# Schematic.net
KiCad netlist of a schematic drawn in Altium Designer
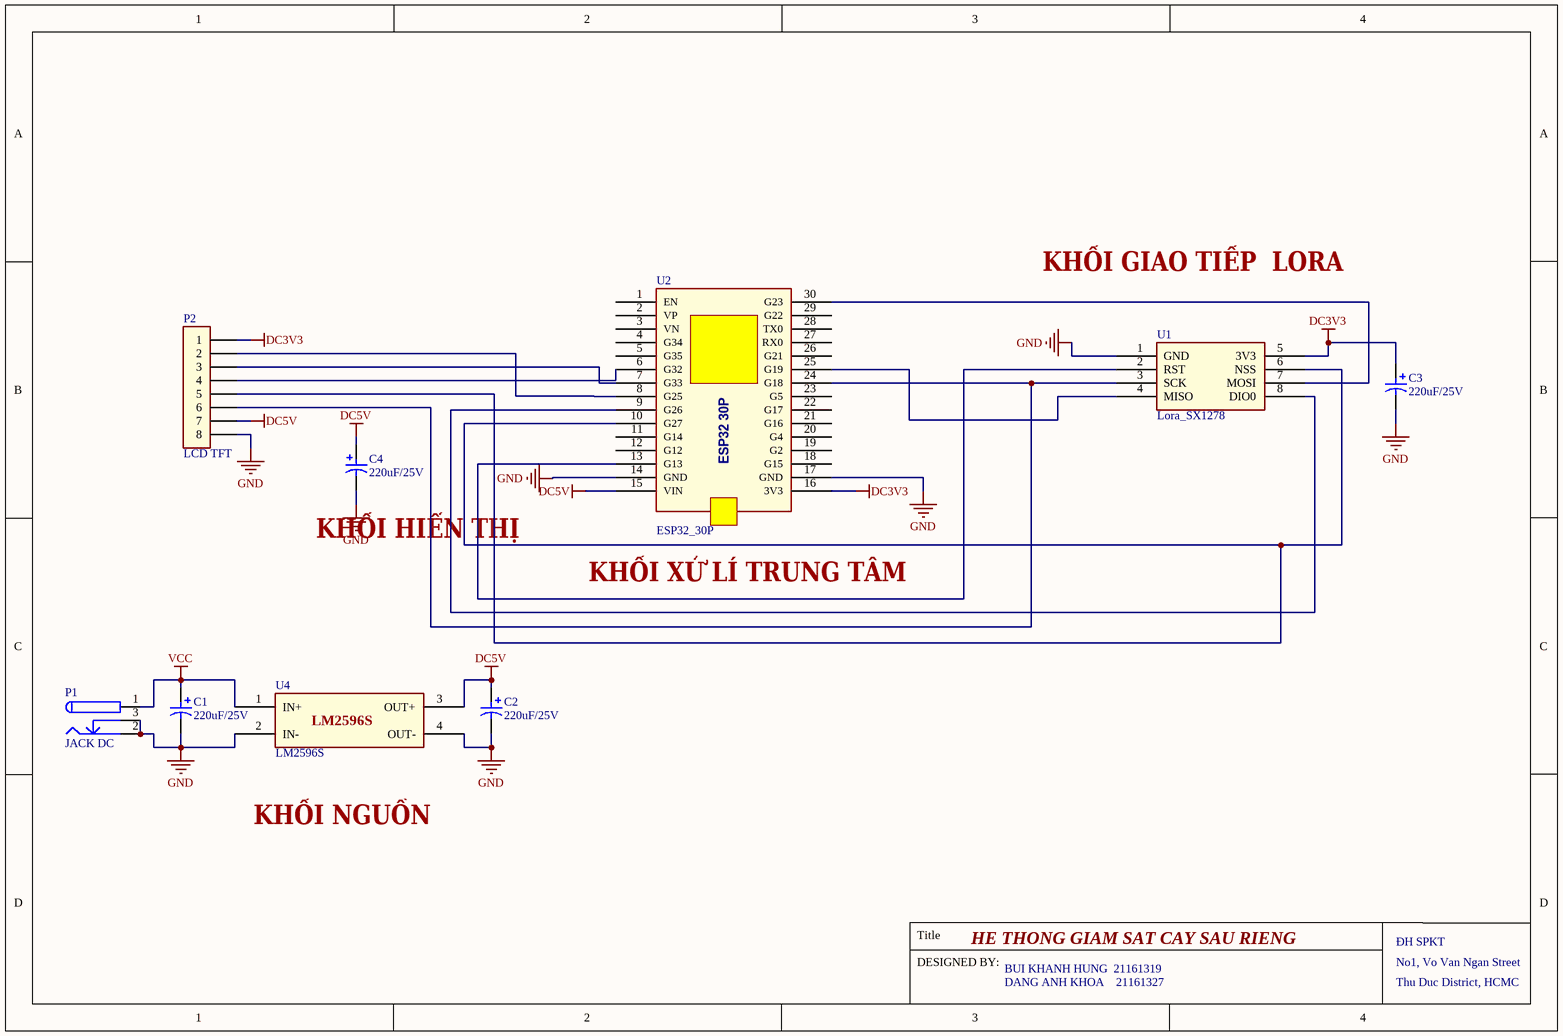
[diagram p0: Schematic.SchDoc]

(export (version "E")
  (design (tool "Eeschema 10.0.6"))
  (components
    (comp (ref "C1")
      (value "220uF/25V")
      (footprint "CAP-ALUM-10x12.5")
      (description "Capacitor Aluminum 220uF 20% 25V Radial")
      (fields (field (name "MPN") "CLA4514"))
      (libsource (lib "SachTranLib") (part "EEUTA1E221"))
    )
    (comp (ref "C2")
      (value "220uF/25V")
      (footprint "CAP-ALUM-10x12.5")
      (description "Capacitor Aluminum 220uF 20% 25V Radial")
      (fields (field (name "MPN") "CLA4514"))
      (libsource (lib "SachTranLib") (part "EEUTA1E221"))
    )
    (comp (ref "C3")
      (value "220uF/25V")
      (footprint "CAP-ALUM-10x12.5")
      (description "Capacitor Aluminum 220uF 20% 25V Radial")
      (fields (field (name "MPN") "CLA4514"))
      (libsource (lib "SachTranLib") (part "EEUTA1E221"))
    )
    (comp (ref "C4")
      (value "220uF/25V")
      (footprint "CAP-ALUM-10x12.5")
      (description "Capacitor Aluminum 220uF 20% 25V Radial")
      (fields (field (name "MPN") "CLA4514"))
      (libsource (lib "") (part "EEUTA1E221_1"))
    )
    (comp (ref "P1")
      (value "JACK DC")
      (footprint "DC5.5/2.1")
      (description "Low Voltage Power Supply Connector")
      (libsource (lib "SachTranLib") (part "DC5.5/2.1"))
    )
    (comp (ref "P2")
      (value "LCD TFT")
      (footprint "B8B-XH-A")
      (description "Connector Header Through Hole 8 position 0.098\" (2.50mm)")
      (libsource (lib "SachTranLib") (part "B8B-XH-A"))
    )
    (comp (ref "U1")
      (value "Lora_SX1278")
      (footprint "Module-LORA-SX1278")
      (description "Module Lora SX1278 RA02 SPI")
      (libsource (lib "SachTranLib") (part "Module-Lora-SX1278-SPI"))
    )
    (comp (ref "U2")
      (value "ESP32_30P")
      (footprint "Kit-ESP32-30P")
      (description "Kit ESP32 30P")
      (libsource (lib "SachTranLib") (part "Kit_ESP32_30P"))
    )
    (comp (ref "U4")
      (value "LM2596S")
      (footprint "Module-LM2596S")
      (description "Module LM2596S")
      (libsource (lib "SachTranLib") (part "Module-LM2596S"))
    )
  )
  (nets
    (net (code "1") (name "DC3V3") (class "Default")
      (node (ref "C3") (pin "1") (pinfunction "1_1") (pintype "passive"))
      (node (ref "P2") (pin "1") (pinfunction "1_1") (pintype "passive"))
      (node (ref "U1") (pin "5") (pinfunction "3V3_5") (pintype "passive"))
      (node (ref "U2") (pin "16") (pinfunction "3V3_16") (pintype "passive"))
    )
    (net (code "2") (name "DC5V") (class "Default")
      (node (ref "C2") (pin "1") (pinfunction "1_1") (pintype "passive"))
      (node (ref "C4") (pin "1") (pinfunction "1_1") (pintype "passive"))
      (node (ref "P2") (pin "7") (pinfunction "7_7") (pintype "passive"))
      (node (ref "U2") (pin "15") (pinfunction "VIN_15") (pintype "passive"))
      (node (ref "U4") (pin "3") (pinfunction "OUT+_3") (pintype "passive"))
    )
    (net (code "3") (name "GND") (class "Default")
      (node (ref "C1") (pin "2") (pinfunction "2_2") (pintype "passive"))
      (node (ref "C2") (pin "2") (pinfunction "2_2") (pintype "passive"))
      (node (ref "C3") (pin "2") (pinfunction "2_2") (pintype "passive"))
      (node (ref "C4") (pin "2") (pinfunction "2_2") (pintype "passive"))
      (node (ref "P1") (pin "2") (pinfunction "2_2") (pintype "power_in"))
      (node (ref "P1") (pin "3") (pinfunction "3_3") (pintype "power_in"))
      (node (ref "P2") (pin "8") (pinfunction "8_8") (pintype "passive"))
      (node (ref "U1") (pin "1") (pinfunction "GND_1") (pintype "passive"))
      (node (ref "U2") (pin "14") (pinfunction "GND_14") (pintype "passive"))
      (node (ref "U2") (pin "17") (pinfunction "GND_17") (pintype "passive"))
      (node (ref "U4") (pin "2") (pinfunction "IN-_2") (pintype "passive"))
      (node (ref "U4") (pin "4") (pinfunction "OUT-_4") (pintype "passive"))
    )
    (net (code "4") (name "Net-(U1-DIO0)") (class "Default")
      (node (ref "U1") (pin "8") (pinfunction "DIO0_8") (pintype "passive"))
      (node (ref "U2") (pin "9") (pinfunction "G26_9") (pintype "passive"))
    )
    (net (code "5") (name "Net-(U1-MISO)") (class "Default")
      (node (ref "U1") (pin "4") (pinfunction "MISO_4") (pintype "passive"))
      (node (ref "U2") (pin "25") (pinfunction "G19_25") (pintype "passive"))
    )
    (net (code "6") (name "Net-(U1-MOSI)") (class "Default")
      (node (ref "U1") (pin "7") (pinfunction "MOSI_7") (pintype "passive"))
      (node (ref "U2") (pin "30") (pinfunction "G23_30") (pintype "passive"))
    )
    (net (code "7") (name "Net-(U1-NSS)") (class "Default")
      (node (ref "P2") (pin "5") (pinfunction "5_5") (pintype "passive"))
      (node (ref "U1") (pin "6") (pinfunction "NSS_6") (pintype "passive"))
      (node (ref "U2") (pin "10") (pinfunction "G27_10") (pintype "passive"))
    )
    (net (code "8") (name "Net-(U1-RST)") (class "Default")
      (node (ref "U1") (pin "2") (pinfunction "RST_2") (pintype "passive"))
      (node (ref "U2") (pin "13") (pinfunction "G13_13") (pintype "passive"))
    )
    (net (code "9") (name "Net-(U1-SCK)") (class "Default")
      (node (ref "P2") (pin "6") (pinfunction "6_6") (pintype "passive"))
      (node (ref "U1") (pin "3") (pinfunction "SCK_3") (pintype "passive"))
      (node (ref "U2") (pin "24") (pinfunction "G18_24") (pintype "passive"))
    )
    (net (code "10") (name "Net-(U2-G25)") (class "Default")
      (node (ref "P2") (pin "2") (pinfunction "2_2") (pintype "passive"))
      (node (ref "U2") (pin "8") (pinfunction "G25_8") (pintype "passive"))
    )
    (net (code "11") (name "Net-(U2-G32)") (class "Default")
      (node (ref "P2") (pin "4") (pinfunction "4_4") (pintype "passive"))
      (node (ref "U2") (pin "6") (pinfunction "G32_6") (pintype "passive"))
    )
    (net (code "12") (name "Net-(U2-G33)") (class "Default")
      (node (ref "P2") (pin "3") (pinfunction "3_3") (pintype "passive"))
      (node (ref "U2") (pin "7") (pinfunction "G33_7") (pintype "passive"))
    )
    (net (code "13") (name "VCC") (class "Default")
      (node (ref "C1") (pin "1") (pinfunction "1_1") (pintype "passive"))
      (node (ref "P1") (pin "1") (pinfunction "1_1") (pintype "power_in"))
      (node (ref "U4") (pin "1") (pinfunction "IN+_1") (pintype "passive"))
    )
    (net (code "14") (name "unconnected-(U2-EN-Pad1)") (class "Default")
      (node (ref "U2") (pin "1") (pinfunction "EN_1") (pintype "passive"))
    )
    (net (code "15") (name "unconnected-(U2-G2-Pad19)") (class "Default")
      (node (ref "U2") (pin "19") (pinfunction "G2_19") (pintype "passive"))
    )
    (net (code "16") (name "unconnected-(U2-G4-Pad20)") (class "Default")
      (node (ref "U2") (pin "20") (pinfunction "G4_20") (pintype "passive"))
    )
    (net (code "17") (name "unconnected-(U2-G5-Pad23)") (class "Default")
      (node (ref "U2") (pin "23") (pinfunction "G5_23") (pintype "passive"))
    )
    (net (code "18") (name "unconnected-(U2-G12-Pad12)") (class "Default")
      (node (ref "U2") (pin "12") (pinfunction "G12_12") (pintype "passive"))
    )
    (net (code "19") (name "unconnected-(U2-G14-Pad11)") (class "Default")
      (node (ref "U2") (pin "11") (pinfunction "G14_11") (pintype "passive"))
    )
    (net (code "20") (name "unconnected-(U2-G15-Pad18)") (class "Default")
      (node (ref "U2") (pin "18") (pinfunction "G15_18") (pintype "passive"))
    )
    (net (code "21") (name "unconnected-(U2-G16-Pad21)") (class "Default")
      (node (ref "U2") (pin "21") (pinfunction "G16_21") (pintype "passive"))
    )
    (net (code "22") (name "unconnected-(U2-G17-Pad22)") (class "Default")
      (node (ref "U2") (pin "22") (pinfunction "G17_22") (pintype "passive"))
    )
    (net (code "23") (name "unconnected-(U2-G21-Pad26)") (class "Default")
      (node (ref "U2") (pin "26") (pinfunction "G21_26") (pintype "passive"))
    )
    (net (code "24") (name "unconnected-(U2-G22-Pad29)") (class "Default")
      (node (ref "U2") (pin "29") (pinfunction "G22_29") (pintype "passive"))
    )
    (net (code "25") (name "unconnected-(U2-G34-Pad4)") (class "Default")
      (node (ref "U2") (pin "4") (pinfunction "G34_4") (pintype "passive"))
    )
    (net (code "26") (name "unconnected-(U2-G35-Pad5)") (class "Default")
      (node (ref "U2") (pin "5") (pinfunction "G35_5") (pintype "passive"))
    )
    (net (code "27") (name "unconnected-(U2-RX0-Pad27)") (class "Default")
      (node (ref "U2") (pin "27") (pinfunction "RX0_27") (pintype "passive"))
    )
    (net (code "28") (name "unconnected-(U2-TX0-Pad28)") (class "Default")
      (node (ref "U2") (pin "28") (pinfunction "TX0_28") (pintype "passive"))
    )
    (net (code "29") (name "unconnected-(U2-VN-Pad3)") (class "Default")
      (node (ref "U2") (pin "3") (pinfunction "VN_3") (pintype "passive"))
    )
    (net (code "30") (name "unconnected-(U2-VP-Pad2)") (class "Default")
      (node (ref "U2") (pin "2") (pinfunction "VP_2") (pintype "passive"))
    )
  )
)
